# buzzer.net
KiCad netlist of a schematic drawn in Altium Designer
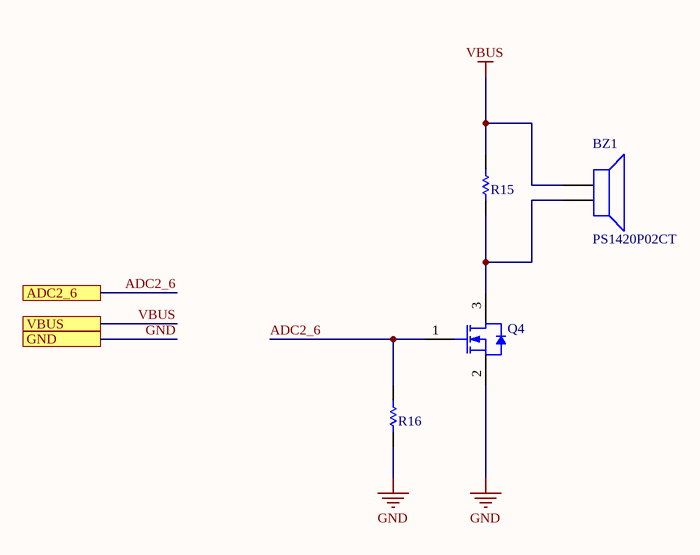
[diagram p0: buzzer.SchDoc]

(export (version "E")
  (design (tool "Eeschema 10.0.6"))
  (components
    (comp (ref "BZ1")
      (value "PS1420P02CT")
      (footprint "Buzz_14mm")
      (description "Buzzers Transducer, Externally Driven Piezo 5V 2kHz 70dB @ 5V, 10cm Through Hole PC Pins")
      (libsource (lib "LIB_FIT") (part "PS1420P02CT"))
    )
    (comp (ref "Q4")
      (value "BSS138-7-F")
      (footprint "DIOD-SOT23-3_V")
      (description "N-Channel Enhancement Mode Mosfet, 50 V, 0.2 A, -55 to 150 degC, 3-Pin SOT23, RoHS, Tape and Reel")
      (fields (field (name "MANUFACTURER") "Diodes Inc"))
      (libsource (lib "Altium Content Vault") (part "NEMOS-GSD-3"))
    )
    (comp (ref "R15")
      (value "ERJ-P06J102V")
      (footprint "RESC2013X70X40NL20T20")
      (description "RES SMD 1K OHM 5% 1/2W 0805")
      (fields (field (name "MANUFACTURER") "Panasonic"))
      (libsource (lib "Altium Content Vault") (part "RES"))
    )
    (comp (ref "R16")
      (value "RK73B2ATTD103J")
      (footprint "RESC2013X60X30NL20T20")
      (fields (field (name "MANUFACTURER") "KOA Speer"))
      (libsource (lib "Altium Content Vault") (part "RES"))
    )
  )
  (nets
    (net (code "1") (name "/ADC2_6") (class "Default")
      (node (ref "Q4") (pin "1") (pinfunction "G_1") (pintype "passive"))
      (node (ref "R16") (pin "1") (pinfunction "1_1") (pintype "passive"))
    )
    (net (code "2") (name "GND") (class "Default")
      (node (ref "Q4") (pin "2") (pinfunction "S_2") (pintype "passive"))
      (node (ref "R16") (pin "2") (pinfunction "2_2") (pintype "passive"))
    )
    (net (code "3") (name "Net-(Q4-D)") (class "Default")
      (node (ref "BZ1") (pin "1") (pinfunction "1_1") (pintype "passive"))
      (node (ref "Q4") (pin "3") (pinfunction "D_3") (pintype "passive"))
      (node (ref "R15") (pin "1") (pinfunction "1_1") (pintype "passive"))
    )
    (net (code "4") (name "VBUS") (class "Default")
      (node (ref "BZ1") (pin "2") (pinfunction "2_2") (pintype "passive"))
      (node (ref "R15") (pin "2") (pinfunction "2_2") (pintype "passive"))
    )
  )
)
